# Digital_SRAM.net
KiCad netlist of a schematic drawn in Altium Designer
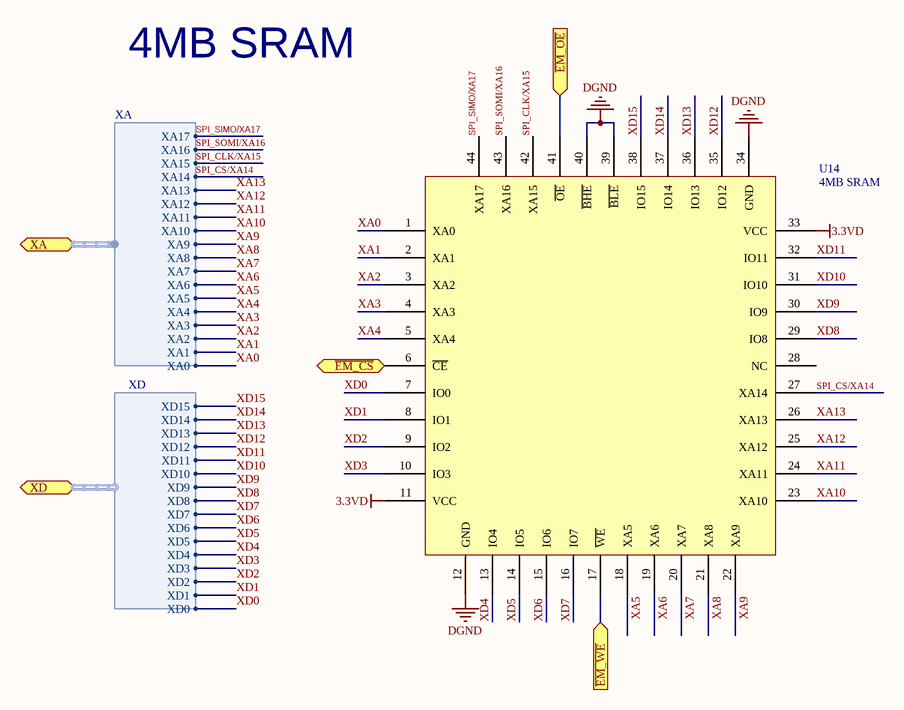
[diagram p0: Digital_SRAM.SchDoc]

(export (version "E")
  (design (tool "Eeschema 10.0.6"))
  (components
    (comp (ref "U14")
      (value "4MB SRAM")
      (footprint "TSOP-44")
      (description "IC SRAM 4MBIT 8NS 44TSOP")
      (libsource (lib "SubjuGator8") (part "CY7C1041CV33-8ZSXI"))
    )
  )
  (nets
    (net (code "3") (name "/SPI_CLK{slash}XA15") (class "Default")
      (node (ref "U14") (pin "42") (pinfunction "XA15_42") (pintype "passive"))
    )
    (net (code "4") (name "/SPI_CS{slash}XA14") (class "Default")
      (node (ref "U14") (pin "27") (pinfunction "XA14_27") (pintype "passive"))
    )
    (net (code "5") (name "/SPI_SIMO{slash}XA17") (class "Default")
      (node (ref "U14") (pin "44") (pinfunction "XA17_44") (pintype "passive"))
    )
    (net (code "6") (name "/SPI_SOMI{slash}XA16") (class "Default")
      (node (ref "U14") (pin "43") (pinfunction "XA16_43") (pintype "passive"))
    )
    (net (code "7") (name "/XA0") (class "Default")
      (node (ref "U14") (pin "1") (pinfunction "XA0_1") (pintype "passive"))
    )
    (net (code "8") (name "/XA1") (class "Default")
      (node (ref "U14") (pin "2") (pinfunction "XA1_2") (pintype "passive"))
    )
    (net (code "9") (name "/XA2") (class "Default")
      (node (ref "U14") (pin "3") (pinfunction "XA2_3") (pintype "passive"))
    )
    (net (code "10") (name "/XA3") (class "Default")
      (node (ref "U14") (pin "4") (pinfunction "XA3_4") (pintype "passive"))
    )
    (net (code "11") (name "/XA4") (class "Default")
      (node (ref "U14") (pin "5") (pinfunction "XA4_5") (pintype "passive"))
    )
    (net (code "12") (name "/XA5") (class "Default")
      (node (ref "U14") (pin "18") (pinfunction "XA5_18") (pintype "passive"))
    )
    (net (code "13") (name "/XA6") (class "Default")
      (node (ref "U14") (pin "19") (pinfunction "XA6_19") (pintype "passive"))
    )
    (net (code "14") (name "/XA7") (class "Default")
      (node (ref "U14") (pin "20") (pinfunction "XA7_20") (pintype "passive"))
    )
    (net (code "15") (name "/XA8") (class "Default")
      (node (ref "U14") (pin "21") (pinfunction "XA8_21") (pintype "passive"))
    )
    (net (code "16") (name "/XA9") (class "Default")
      (node (ref "U14") (pin "22") (pinfunction "XA9_22") (pintype "passive"))
    )
    (net (code "17") (name "/XA10") (class "Default")
      (node (ref "U14") (pin "23") (pinfunction "XA10_23") (pintype "passive"))
    )
    (net (code "18") (name "/XA11") (class "Default")
      (node (ref "U14") (pin "24") (pinfunction "XA11_24") (pintype "passive"))
    )
    (net (code "19") (name "/XA12") (class "Default")
      (node (ref "U14") (pin "25") (pinfunction "XA12_25") (pintype "passive"))
    )
    (net (code "20") (name "/XA13") (class "Default")
      (node (ref "U14") (pin "26") (pinfunction "XA13_26") (pintype "passive"))
    )
    (net (code "21") (name "/XD0") (class "Default")
      (node (ref "U14") (pin "7") (pinfunction "IO0_7") (pintype "passive"))
    )
    (net (code "22") (name "/XD1") (class "Default")
      (node (ref "U14") (pin "8") (pinfunction "IO1_8") (pintype "passive"))
    )
    (net (code "23") (name "/XD2") (class "Default")
      (node (ref "U14") (pin "9") (pinfunction "IO2_9") (pintype "passive"))
    )
    (net (code "24") (name "/XD3") (class "Default")
      (node (ref "U14") (pin "10") (pinfunction "IO3_10") (pintype "passive"))
    )
    (net (code "25") (name "/XD4") (class "Default")
      (node (ref "U14") (pin "13") (pinfunction "IO4_13") (pintype "passive"))
    )
    (net (code "26") (name "/XD5") (class "Default")
      (node (ref "U14") (pin "14") (pinfunction "IO5_14") (pintype "passive"))
    )
    (net (code "27") (name "/XD6") (class "Default")
      (node (ref "U14") (pin "15") (pinfunction "IO6_15") (pintype "passive"))
    )
    (net (code "28") (name "/XD7") (class "Default")
      (node (ref "U14") (pin "16") (pinfunction "IO7_16") (pintype "passive"))
    )
    (net (code "29") (name "/XD8") (class "Default")
      (node (ref "U14") (pin "29") (pinfunction "IO8_29") (pintype "passive"))
    )
    (net (code "30") (name "/XD9") (class "Default")
      (node (ref "U14") (pin "30") (pinfunction "IO9_30") (pintype "passive"))
    )
    (net (code "31") (name "/XD10") (class "Default")
      (node (ref "U14") (pin "31") (pinfunction "IO10_31") (pintype "passive"))
    )
    (net (code "32") (name "/XD11") (class "Default")
      (node (ref "U14") (pin "32") (pinfunction "IO11_32") (pintype "passive"))
    )
    (net (code "33") (name "/XD12") (class "Default")
      (node (ref "U14") (pin "35") (pinfunction "IO12_35") (pintype "passive"))
    )
    (net (code "34") (name "/XD13") (class "Default")
      (node (ref "U14") (pin "36") (pinfunction "IO13_36") (pintype "passive"))
    )
    (net (code "35") (name "/XD14") (class "Default")
      (node (ref "U14") (pin "37") (pinfunction "IO14_37") (pintype "passive"))
    )
    (net (code "36") (name "/XD15") (class "Default")
      (node (ref "U14") (pin "38") (pinfunction "IO15_38") (pintype "passive"))
    )
    (net (code "39") (name "/~{EM_CS}") (class "Default")
      (node (ref "U14") (pin "6") (pinfunction "~{CE}_6") (pintype "passive"))
    )
    (net (code "40") (name "/~{EM_OE}") (class "Default")
      (node (ref "U14") (pin "41") (pinfunction "~{OE}_41") (pintype "passive"))
    )
    (net (code "41") (name "/~{EM_WE}") (class "Default")
      (node (ref "U14") (pin "17") (pinfunction "~{WE}_17") (pintype "passive"))
    )
    (net (code "42") (name "3.3VD") (class "Default")
      (node (ref "U14") (pin "11") (pinfunction "VCC_11") (pintype "passive"))
      (node (ref "U14") (pin "33") (pinfunction "VCC_33") (pintype "passive"))
    )
    (net (code "43") (name "DGND") (class "Default")
      (node (ref "U14") (pin "12") (pinfunction "GND_12") (pintype "passive"))
      (node (ref "U14") (pin "34") (pinfunction "GND_34") (pintype "passive"))
      (node (ref "U14") (pin "39") (pinfunction "~{BLE}_39") (pintype "passive"))
      (node (ref "U14") (pin "40") (pinfunction "~{BHE}_40") (pintype "passive"))
    )
    (net (code "44") (name "unconnected-(U14-NC-Pad28)") (class "Default")
      (node (ref "U14") (pin "28") (pinfunction "NC_28") (pintype "passive"))
    )
  )
)
